# SCH_Visit_cards_2024-08-08.net
KiCad netlist of a schematic drawn in EasyEDA
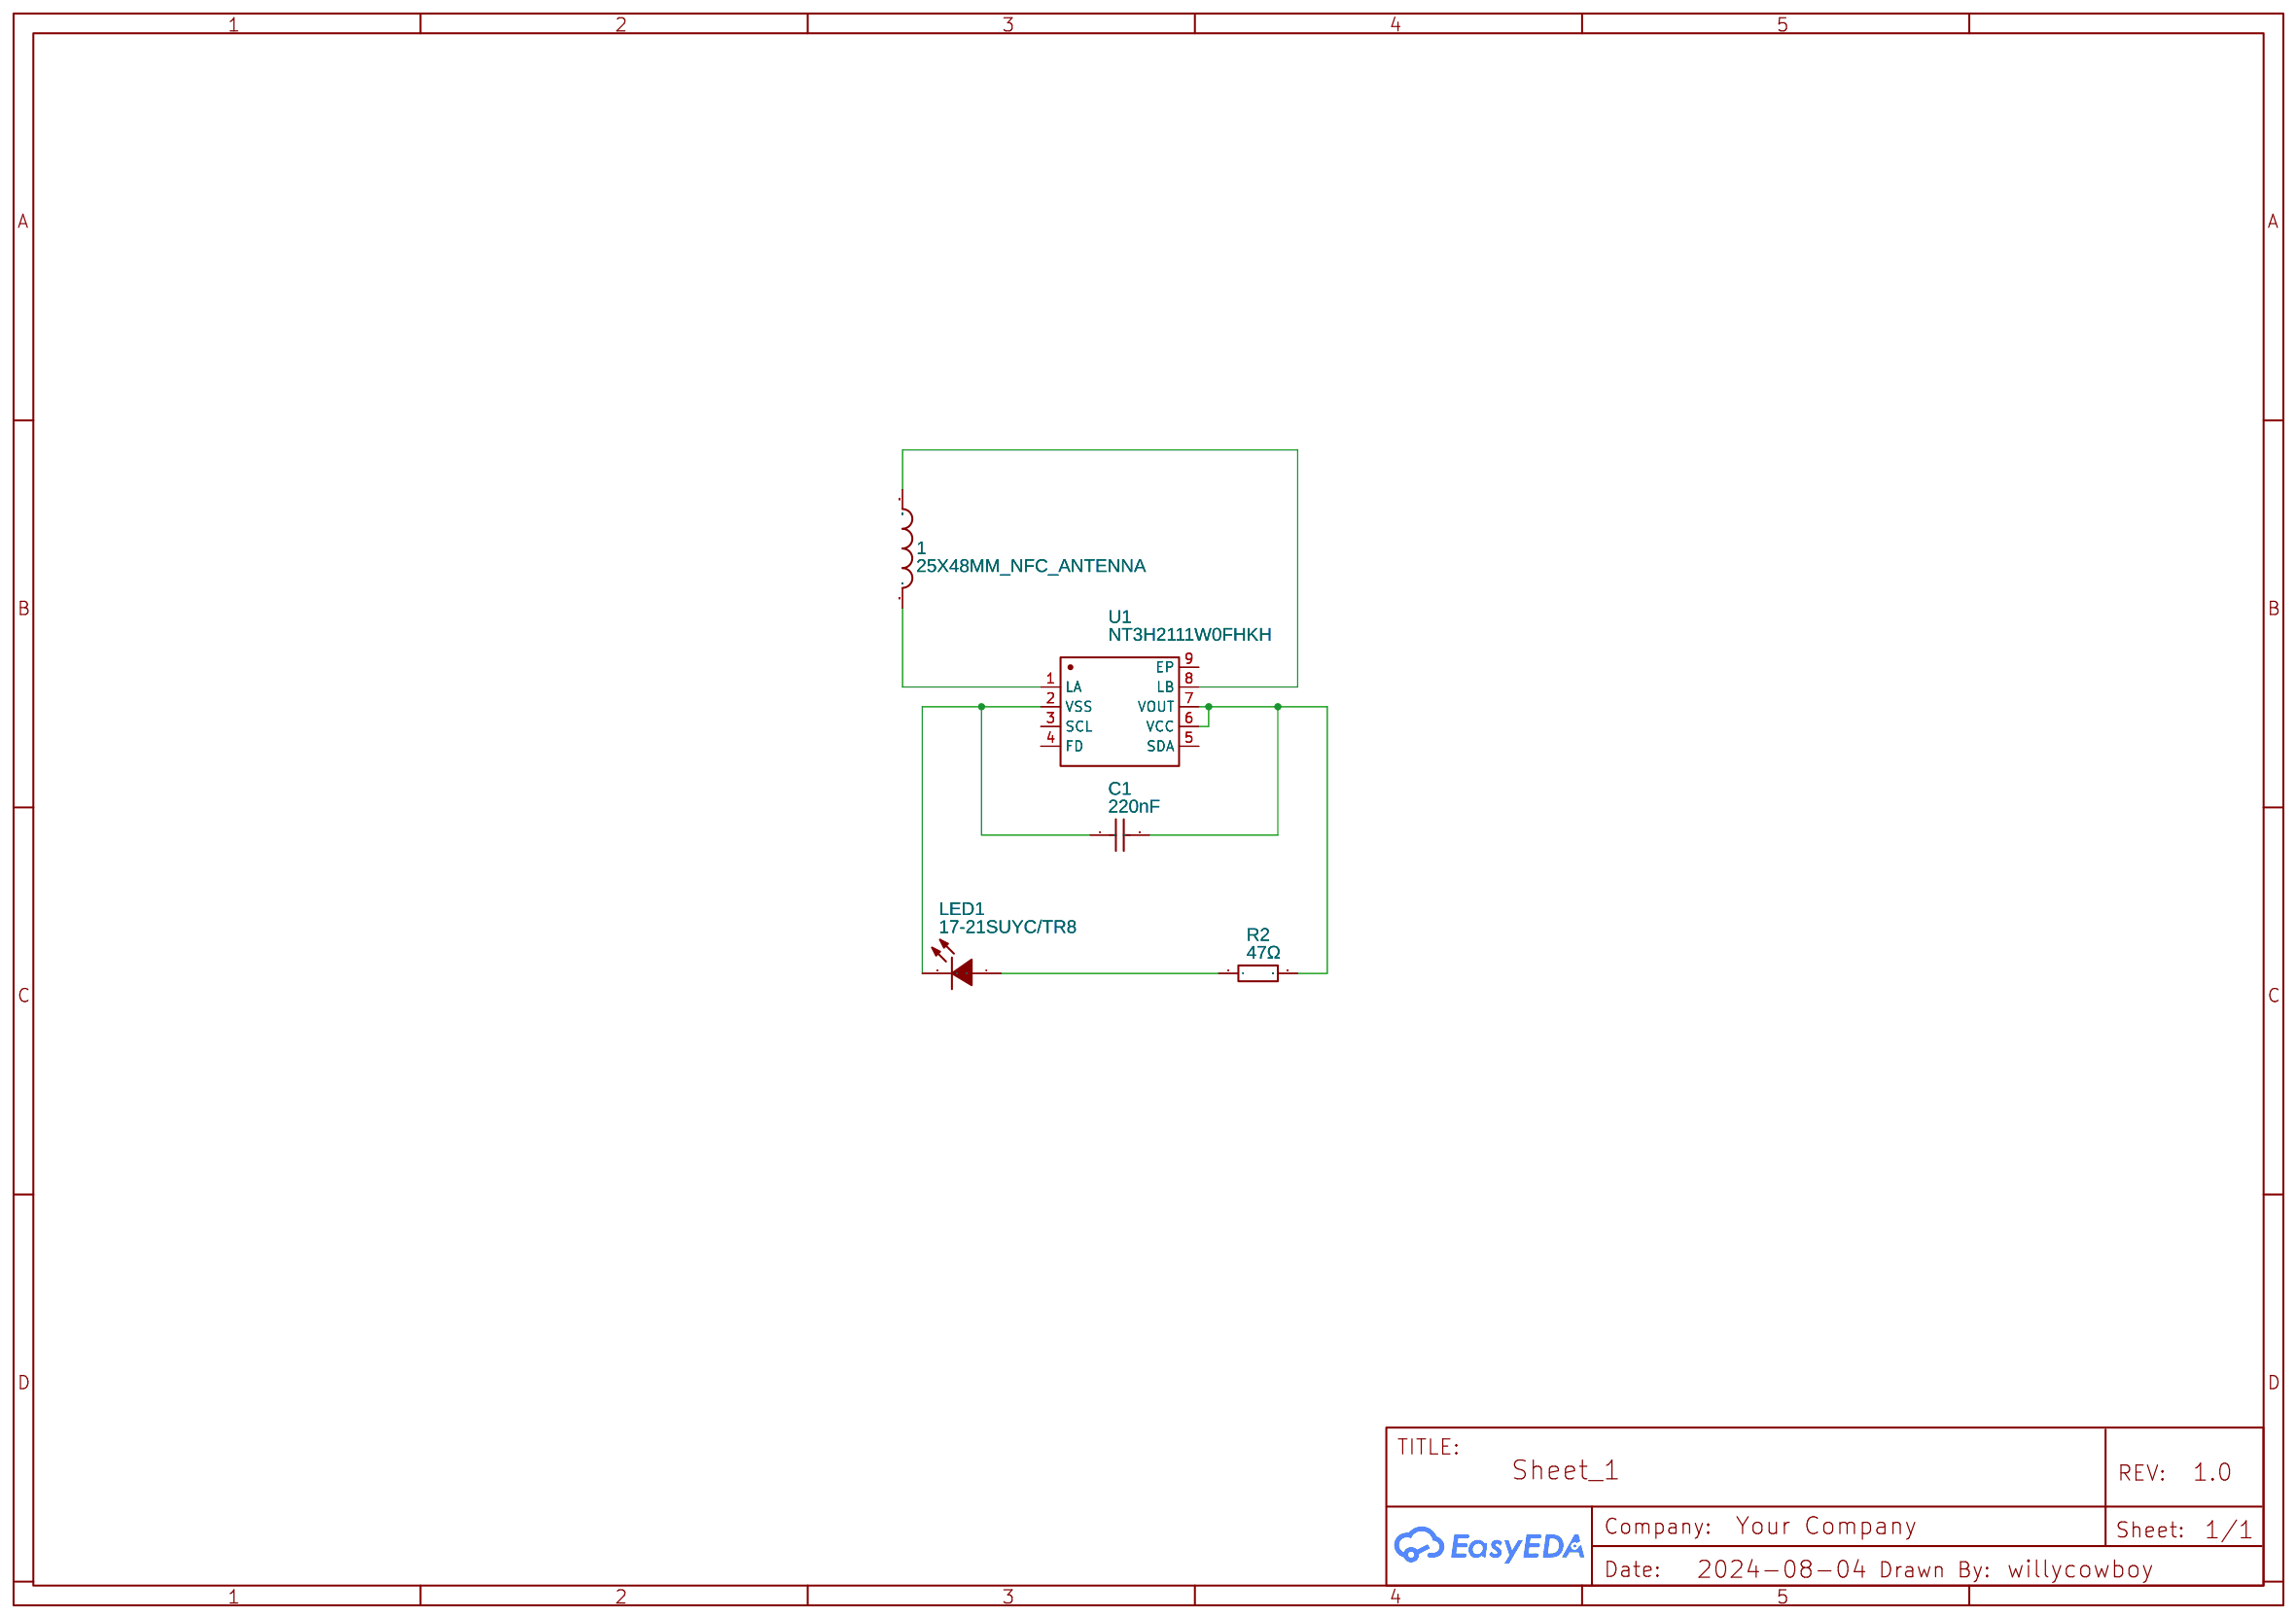
[diagram p0: schematic sheet]

(export (version "E")
  (design (tool "Eeschema 10.0.6"))
  (components
    (comp (ref "1") (value "25X48MM_NFC_ANTENNA") (libsource (lib "") (part "25X48MM_NFC_ANTENNA")))
    (comp (ref "C1")
      (value "220nF")
      (fields
        (field (name "Manufacturer Part") "CL10B224KA8NNNC")
        (field (name "Manufacturer") "SAMSUNG(三星)")
      )
      (libsource (lib "") (part "CL10B224KA8NNNC"))
    )
    (comp (ref "LED1")
      (value "17-21SUYC/TR8")
      (fields (field (name "Manufacturer Part") "KT-0805黄灯") (field (name "Manufacturer") "KENTO"))
      (libsource (lib "") (part "17-21SUYC/TR8"))
    )
    (comp (ref "R2")
      (value "47Ω")
      (fields
        (field (name "Manufacturer Part") "0603WAF470JT5E")
        (field (name "Manufacturer") "UNI-ROYAL(厚声)")
      )
      (libsource (lib "") (part "0603WAF470JT5E"))
    )
    (comp (ref "U1")
      (value "NT3H2111W0FHKH")
      (fields (field (name "Manufacturer") "NXP(恩智浦)"))
      (libsource (lib "") (part "NT3H2111W0FHKH"))
    )
  )
  (nets
    (net (code "1") (name "Net-(LED1-+)") (class "Default")
      (node (ref "LED1") (pin "1") (pinfunction "+_1") (pintype "unspecified"))
      (node (ref "R2") (pin "1") (pinfunction "1_1") (pintype "input"))
    )
    (net (code "2") (name "Net-(LED1--)") (class "Default")
      (node (ref "C1") (pin "1") (pinfunction "1_1") (pintype "input"))
      (node (ref "LED1") (pin "2") (pinfunction "-_2") (pintype "unspecified"))
      (node (ref "U1") (pin "2") (pinfunction "VSS_2") (pintype "unspecified"))
    )
    (net (code "3") (name "Net-(U1-LA)") (class "Default")
      (node (ref "1") (pin "P$2") (pinfunction "P$2_P$2") (pintype "bidirectional"))
      (node (ref "U1") (pin "1") (pinfunction "LA_1") (pintype "unspecified"))
    )
    (net (code "4") (name "Net-(U1-LB)") (class "Default")
      (node (ref "1") (pin "P$1") (pinfunction "P$1_P$1") (pintype "bidirectional"))
      (node (ref "U1") (pin "8") (pinfunction "LB_8") (pintype "unspecified"))
    )
    (net (code "5") (name "Net-(U1-VCC)") (class "Default")
      (node (ref "C1") (pin "2") (pinfunction "2_2") (pintype "input"))
      (node (ref "R2") (pin "2") (pinfunction "2_2") (pintype "input"))
      (node (ref "U1") (pin "6") (pinfunction "VCC_6") (pintype "unspecified"))
      (node (ref "U1") (pin "7") (pinfunction "VOUT_7") (pintype "unspecified"))
    )
    (net (code "6") (name "unconnected-(U1-EP-Pad9)") (class "Default")
      (node (ref "U1") (pin "9") (pinfunction "EP_9") (pintype "unspecified"))
    )
    (net (code "7") (name "unconnected-(U1-FD-Pad4)") (class "Default")
      (node (ref "U1") (pin "4") (pinfunction "FD_4") (pintype "unspecified"))
    )
    (net (code "8") (name "unconnected-(U1-SCL-Pad3)") (class "Default")
      (node (ref "U1") (pin "3") (pinfunction "SCL_3") (pintype "unspecified"))
    )
    (net (code "9") (name "unconnected-(U1-SDA-Pad5)") (class "Default")
      (node (ref "U1") (pin "5") (pinfunction "SDA_5") (pintype "unspecified"))
    )
  )
)
